# DUTchMate_rev_a.net
KiCad netlist of a schematic drawn in EAGLE
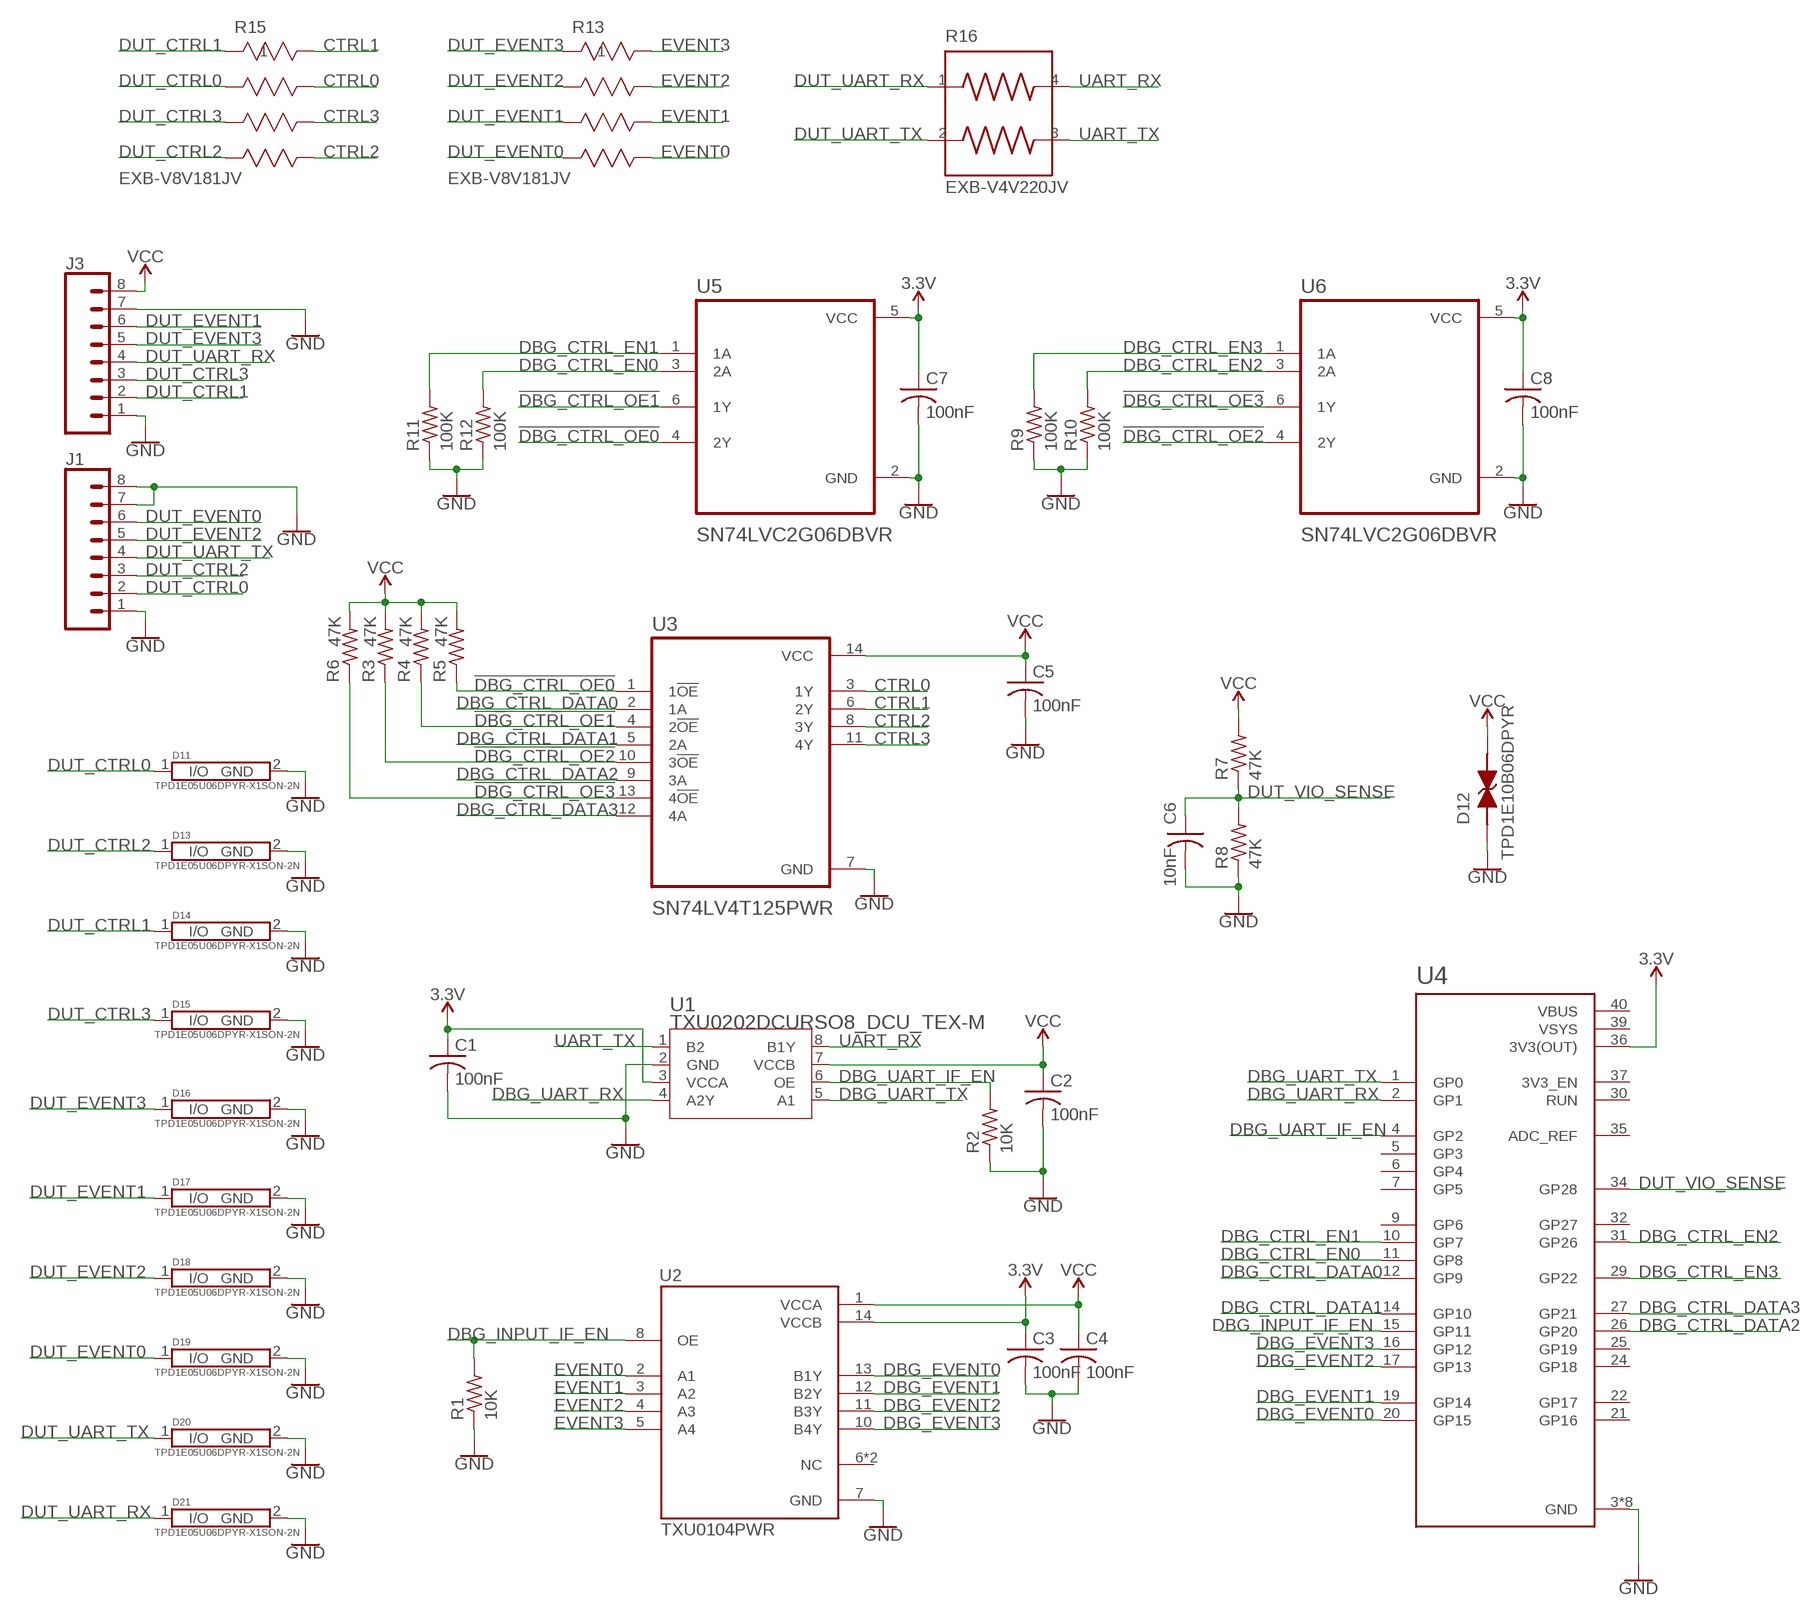
[diagram p0: schematic, sheet 1]

(export (version "E")
  (design (tool "Eeschema 10.0.6"))
  (components
    (comp (ref "C1")
      (value "100nF")
      (footprint "eagle-import:C0805K")
      (libsource (lib "eagle-import") (part "C-USC0805K"))
    )
    (comp (ref "C2")
      (value "100nF")
      (footprint "eagle-import:C0805K")
      (libsource (lib "eagle-import") (part "C-USC0805K"))
    )
    (comp (ref "C3")
      (value "100nF")
      (footprint "eagle-import:C0805K")
      (libsource (lib "eagle-import") (part "C-USC0805K"))
    )
    (comp (ref "C4")
      (value "100nF")
      (footprint "eagle-import:C0805K")
      (libsource (lib "eagle-import") (part "C-USC0805K"))
    )
    (comp (ref "C5")
      (value "100nF")
      (footprint "eagle-import:C0805K")
      (libsource (lib "eagle-import") (part "C-USC0805K"))
    )
    (comp (ref "C6")
      (value "10nF")
      (footprint "eagle-import:C0805K")
      (libsource (lib "eagle-import") (part "C-USC0805K"))
    )
    (comp (ref "C7")
      (value "100nF")
      (footprint "eagle-import:C0805K")
      (libsource (lib "eagle-import") (part "C-USC0805K"))
    )
    (comp (ref "C8")
      (value "100nF")
      (footprint "eagle-import:C0805K")
      (libsource (lib "eagle-import") (part "C-USC0805K"))
    )
    (comp (ref "D11")
      (value "TPD1E05U06DPYR-X1SON-2N")
      (footprint "eagle-import:X1SON-2N")
      (libsource (lib "eagle-import") (part "TPD1E05U06DPYR-X1SON-2N"))
    )
    (comp (ref "D12")
      (value "TPD1E10B06DPYR")
      (footprint "eagle-import:DIO_TPD1E10B06DPYR")
      (fields (field (name "MF") "Texas Instruments"))
      (libsource (lib "eagle-import") (part "TPD1E10B06DPYR"))
    )
    (comp (ref "D13")
      (value "TPD1E05U06DPYR-X1SON-2N")
      (footprint "eagle-import:X1SON-2N")
      (libsource (lib "eagle-import") (part "TPD1E05U06DPYR-X1SON-2N"))
    )
    (comp (ref "D14")
      (value "TPD1E05U06DPYR-X1SON-2N")
      (footprint "eagle-import:X1SON-2N")
      (libsource (lib "eagle-import") (part "TPD1E05U06DPYR-X1SON-2N"))
    )
    (comp (ref "D15")
      (value "TPD1E05U06DPYR-X1SON-2N")
      (footprint "eagle-import:X1SON-2N")
      (libsource (lib "eagle-import") (part "TPD1E05U06DPYR-X1SON-2N"))
    )
    (comp (ref "D16")
      (value "TPD1E05U06DPYR-X1SON-2N")
      (footprint "eagle-import:X1SON-2N")
      (libsource (lib "eagle-import") (part "TPD1E05U06DPYR-X1SON-2N"))
    )
    (comp (ref "D17")
      (value "TPD1E05U06DPYR-X1SON-2N")
      (footprint "eagle-import:X1SON-2N")
      (libsource (lib "eagle-import") (part "TPD1E05U06DPYR-X1SON-2N"))
    )
    (comp (ref "D18")
      (value "TPD1E05U06DPYR-X1SON-2N")
      (footprint "eagle-import:X1SON-2N")
      (libsource (lib "eagle-import") (part "TPD1E05U06DPYR-X1SON-2N"))
    )
    (comp (ref "D19")
      (value "TPD1E05U06DPYR-X1SON-2N")
      (footprint "eagle-import:X1SON-2N")
      (libsource (lib "eagle-import") (part "TPD1E05U06DPYR-X1SON-2N"))
    )
    (comp (ref "D20")
      (value "TPD1E05U06DPYR-X1SON-2N")
      (footprint "eagle-import:X1SON-2N")
      (libsource (lib "eagle-import") (part "TPD1E05U06DPYR-X1SON-2N"))
    )
    (comp (ref "D21")
      (value "TPD1E05U06DPYR-X1SON-2N")
      (footprint "eagle-import:X1SON-2N")
      (libsource (lib "eagle-import") (part "TPD1E05U06DPYR-X1SON-2N"))
    )
    (comp (ref "J1")
      (value "CONN_08NO_SILK_FEMALE_PTH")
      (footprint "eagle-import:1X08_NO_SILK")
      (libsource (lib "eagle-import") (part "CONN_08NO_SILK_FEMALE_PTH"))
    )
    (comp (ref "J3")
      (value "CONN_08NO_SILK_FEMALE_PTH")
      (footprint "eagle-import:1X08_NO_SILK")
      (libsource (lib "eagle-import") (part "CONN_08NO_SILK_FEMALE_PTH"))
    )
    (comp (ref "R1")
      (value "10K")
      (footprint "eagle-import:R0603")
      (libsource (lib "eagle-import") (part "R-US_R0603"))
    )
    (comp (ref "R2")
      (value "10K")
      (footprint "eagle-import:R0603")
      (libsource (lib "eagle-import") (part "R-US_R0603"))
    )
    (comp (ref "R3")
      (value "47K")
      (footprint "eagle-import:R0603")
      (libsource (lib "eagle-import") (part "R-US_R0603"))
    )
    (comp (ref "R4")
      (value "47K")
      (footprint "eagle-import:R0603")
      (libsource (lib "eagle-import") (part "R-US_R0603"))
    )
    (comp (ref "R5")
      (value "47K")
      (footprint "eagle-import:R0603")
      (libsource (lib "eagle-import") (part "R-US_R0603"))
    )
    (comp (ref "R6")
      (value "47K")
      (footprint "eagle-import:R0603")
      (libsource (lib "eagle-import") (part "R-US_R0603"))
    )
    (comp (ref "R7")
      (value "47K")
      (footprint "eagle-import:R0603")
      (libsource (lib "eagle-import") (part "R-US_R0603"))
    )
    (comp (ref "R8")
      (value "47K")
      (footprint "eagle-import:R0603")
      (libsource (lib "eagle-import") (part "R-US_R0603"))
    )
    (comp (ref "R9")
      (value "100K")
      (footprint "eagle-import:R0603")
      (libsource (lib "eagle-import") (part "R-US_R0603"))
    )
    (comp (ref "R10")
      (value "100K")
      (footprint "eagle-import:R0603")
      (libsource (lib "eagle-import") (part "R-US_R0603"))
    )
    (comp (ref "R11")
      (value "100K")
      (footprint "eagle-import:R0603")
      (libsource (lib "eagle-import") (part "R-US_R0603"))
    )
    (comp (ref "R12")
      (value "100K")
      (footprint "eagle-import:R0603")
      (libsource (lib "eagle-import") (part "R-US_R0603"))
    )
    (comp (ref "R13")
      (value "EXB-V8V181JV")
      (footprint "eagle-import:EXBV8V_PAN-M")
      (fields
        (field (name "MANUFACTURER_PART_NUMBER") "EXB-V8V102JV")
        (field (name "COPYRIGHT") "Copyright (C) 2026 Ultra Librarian. All rights reserved.")
      )
      (libsource (lib "eagle-import") (part "EXB-V8V102JVEXBV8V_PAN-M"))
    )
    (comp (ref "R15")
      (value "EXB-V8V181JV")
      (footprint "eagle-import:EXBV8V_PAN-M")
      (fields
        (field (name "MANUFACTURER_PART_NUMBER") "EXB-V8V102JV")
        (field (name "COPYRIGHT") "Copyright (C) 2026 Ultra Librarian. All rights reserved.")
      )
      (libsource (lib "eagle-import") (part "EXB-V8V102JVEXBV8V_PAN-M"))
    )
    (comp (ref "R16")
      (value "EXB-V4V220JV")
      (footprint "eagle-import:RESCAV80P160X160X70-4N")
      (fields
        (field (name "DIGIKEY_PART_NUMBER") "Y2472CT-ND")
        (field (name "MF") "Panasonic")
        (field (name "MP") "EXBV4V472JV")
      )
      (libsource (lib "eagle-import") (part "EXB-V4V472JV"))
    )
    (comp (ref "U1")
      (value "TXU0202DCURSO8_DCU_TEX-M")
      (footprint "eagle-import:SO8_DCU_TEX-M")
      (fields
        (field (name "MANUFACTURER_PART_NUMBER") "TXU0202DCUR")
        (field (name "COPYRIGHT") "Copyright (C) 2026 Ultra Librarian. All rights reserved.")
      )
      (libsource (lib "eagle-import") (part "TXU0202DCURSO8_DCU_TEX-M"))
    )
    (comp (ref "U2")
      (value "TXU0104PWR")
      (footprint "eagle-import:SOP65P640X120-14N")
      (fields (field (name "MF") "Texas Instruments"))
      (libsource (lib "eagle-import") (part "TXU0104PWR"))
    )
    (comp (ref "U3")
      (value "SN74LV4T125PWR")
      (footprint "eagle-import:SOP65P640X120-14N")
      (fields (field (name "MF") "Texas Instruments"))
      (libsource (lib "eagle-import") (part "SN74LV4T125PWR"))
    )
    (comp (ref "U4")
      (value "RASPBERRY_PICO-NO_DEBUGPICO-PKG-TH-NO_DEBUG")
      (footprint "eagle-import:PICO-PKG-TH")
      (libsource (lib "eagle-import") (part "RASPBERRY_PICO-NO_DEBUGPICO-PKG-TH-NO_DEBUG"))
    )
    (comp (ref "U5")
      (value "SN74LVC2G06DBVR")
      (footprint "eagle-import:SOT95P280X145-6N")
      (fields (field (name "MF") "Texas Instruments"))
      (libsource (lib "eagle-import") (part "SN74LVC2G06DBVR"))
    )
    (comp (ref "U6")
      (value "SN74LVC2G06DBVR")
      (footprint "eagle-import:SOT95P280X145-6N")
      (fields (field (name "MF") "Texas Instruments"))
      (libsource (lib "eagle-import") (part "SN74LVC2G06DBVR"))
    )
  )
  (nets
    (net (code "1") (name "/CTRL0") (class "Default")
      (node (ref "R15") (pin "7") (pinfunction "7_7") (pintype "passive"))
      (node (ref "U3") (pin "3") (pinfunction "1Y_3") (pintype "output"))
    )
    (net (code "2") (name "/CTRL1") (class "Default")
      (node (ref "R15") (pin "8") (pinfunction "8_8") (pintype "passive"))
      (node (ref "U3") (pin "6") (pinfunction "2Y_6") (pintype "output"))
    )
    (net (code "3") (name "/CTRL2") (class "Default")
      (node (ref "R15") (pin "5") (pinfunction "5_5") (pintype "passive"))
      (node (ref "U3") (pin "8") (pinfunction "3Y_8") (pintype "output"))
    )
    (net (code "4") (name "/CTRL3") (class "Default")
      (node (ref "R15") (pin "6") (pinfunction "6_6") (pintype "passive"))
      (node (ref "U3") (pin "11") (pinfunction "4Y_11") (pintype "output"))
    )
    (net (code "5") (name "/DBG_CTRL_DATA0") (class "Default")
      (node (ref "U3") (pin "2") (pinfunction "1A_2") (pintype "input"))
      (node (ref "U4") (pin "12") (pinfunction "GP9_12") (pintype "bidirectional"))
    )
    (net (code "6") (name "/DBG_CTRL_DATA1") (class "Default")
      (node (ref "U3") (pin "5") (pinfunction "2A_5") (pintype "input"))
      (node (ref "U4") (pin "14") (pinfunction "GP10_14") (pintype "bidirectional"))
    )
    (net (code "7") (name "/DBG_CTRL_DATA2") (class "Default")
      (node (ref "U3") (pin "9") (pinfunction "3A_9") (pintype "input"))
      (node (ref "U4") (pin "26") (pinfunction "GP20_26") (pintype "bidirectional"))
    )
    (net (code "8") (name "/DBG_CTRL_DATA3") (class "Default")
      (node (ref "U3") (pin "12") (pinfunction "4A_12") (pintype "input"))
      (node (ref "U4") (pin "27") (pinfunction "GP21_27") (pintype "bidirectional"))
    )
    (net (code "9") (name "/DBG_CTRL_EN0") (class "Default")
      (node (ref "R12") (pin "2") (pinfunction "2_2") (pintype "passive"))
      (node (ref "U4") (pin "11") (pinfunction "GP8_11") (pintype "bidirectional"))
      (node (ref "U5") (pin "3") (pinfunction "2A_3") (pintype "input"))
    )
    (net (code "10") (name "/DBG_CTRL_EN1") (class "Default")
      (node (ref "R11") (pin "2") (pinfunction "2_2") (pintype "passive"))
      (node (ref "U4") (pin "10") (pinfunction "GP7_10") (pintype "bidirectional"))
      (node (ref "U5") (pin "1") (pinfunction "1A_1") (pintype "input"))
    )
    (net (code "11") (name "/DBG_CTRL_EN2") (class "Default")
      (node (ref "R10") (pin "2") (pinfunction "2_2") (pintype "passive"))
      (node (ref "U4") (pin "31") (pinfunction "GP26_31") (pintype "bidirectional"))
      (node (ref "U6") (pin "3") (pinfunction "2A_3") (pintype "input"))
    )
    (net (code "12") (name "/DBG_CTRL_EN3") (class "Default")
      (node (ref "R9") (pin "2") (pinfunction "2_2") (pintype "passive"))
      (node (ref "U4") (pin "29") (pinfunction "GP22_29") (pintype "bidirectional"))
      (node (ref "U6") (pin "1") (pinfunction "1A_1") (pintype "input"))
    )
    (net (code "13") (name "/DBG_EVENT0") (class "Default")
      (node (ref "U2") (pin "13") (pinfunction "B1Y_13") (pintype "output"))
      (node (ref "U4") (pin "20") (pinfunction "GP15_20") (pintype "bidirectional"))
    )
    (net (code "14") (name "/DBG_EVENT1") (class "Default")
      (node (ref "U2") (pin "12") (pinfunction "B2Y_12") (pintype "output"))
      (node (ref "U4") (pin "19") (pinfunction "GP14_19") (pintype "bidirectional"))
    )
    (net (code "15") (name "/DBG_EVENT2") (class "Default")
      (node (ref "U2") (pin "11") (pinfunction "B3Y_11") (pintype "output"))
      (node (ref "U4") (pin "17") (pinfunction "GP13_17") (pintype "bidirectional"))
    )
    (net (code "16") (name "/DBG_EVENT3") (class "Default")
      (node (ref "U2") (pin "10") (pinfunction "B4Y_10") (pintype "output"))
      (node (ref "U4") (pin "16") (pinfunction "GP12_16") (pintype "bidirectional"))
    )
    (net (code "17") (name "/DBG_INPUT_IF_EN") (class "Default")
      (node (ref "R1") (pin "2") (pinfunction "2_2") (pintype "passive"))
      (node (ref "U2") (pin "8") (pinfunction "OE_8") (pintype "input"))
      (node (ref "U4") (pin "15") (pinfunction "GP11_15") (pintype "bidirectional"))
    )
    (net (code "18") (name "/DBG_UART_IF_EN") (class "Default")
      (node (ref "R2") (pin "2") (pinfunction "2_2") (pintype "passive"))
      (node (ref "U1") (pin "6") (pinfunction "OE_6") (pintype "input"))
      (node (ref "U4") (pin "4") (pinfunction "GP2_4") (pintype "bidirectional"))
    )
    (net (code "19") (name "/DBG_UART_RX") (class "Default")
      (node (ref "U1") (pin "4") (pinfunction "A2Y_4") (pintype "output"))
      (node (ref "U4") (pin "2") (pinfunction "GP1_2") (pintype "bidirectional"))
    )
    (net (code "20") (name "/DBG_UART_TX") (class "Default")
      (node (ref "U1") (pin "5") (pinfunction "A1_5") (pintype "input"))
      (node (ref "U4") (pin "1") (pinfunction "GP0_1") (pintype "bidirectional"))
    )
    (net (code "21") (name "/DUT_CTRL0") (class "Default")
      (node (ref "D11") (pin "1") (pinfunction "I/O_1") (pintype "bidirectional"))
      (node (ref "J1") (pin "2") (pinfunction "2_2") (pintype "passive"))
      (node (ref "R15") (pin "2") (pinfunction "2_2") (pintype "passive"))
    )
    (net (code "22") (name "/DUT_CTRL1") (class "Default")
      (node (ref "D14") (pin "1") (pinfunction "I/O_1") (pintype "bidirectional"))
      (node (ref "J3") (pin "2") (pinfunction "2_2") (pintype "passive"))
      (node (ref "R15") (pin "1") (pinfunction "1_1") (pintype "passive"))
    )
    (net (code "23") (name "/DUT_CTRL2") (class "Default")
      (node (ref "D13") (pin "1") (pinfunction "I/O_1") (pintype "bidirectional"))
      (node (ref "J1") (pin "3") (pinfunction "3_3") (pintype "passive"))
      (node (ref "R15") (pin "4") (pinfunction "4_4") (pintype "passive"))
    )
    (net (code "24") (name "/DUT_CTRL3") (class "Default")
      (node (ref "D15") (pin "1") (pinfunction "I/O_1") (pintype "bidirectional"))
      (node (ref "J3") (pin "3") (pinfunction "3_3") (pintype "passive"))
      (node (ref "R15") (pin "3") (pinfunction "3_3") (pintype "passive"))
    )
    (net (code "25") (name "/DUT_EVENT0") (class "Default")
      (node (ref "D19") (pin "1") (pinfunction "I/O_1") (pintype "bidirectional"))
      (node (ref "J1") (pin "6") (pinfunction "6_6") (pintype "passive"))
      (node (ref "R13") (pin "4") (pinfunction "4_4") (pintype "passive"))
    )
    (net (code "26") (name "/DUT_EVENT1") (class "Default")
      (node (ref "D17") (pin "1") (pinfunction "I/O_1") (pintype "bidirectional"))
      (node (ref "J3") (pin "6") (pinfunction "6_6") (pintype "passive"))
      (node (ref "R13") (pin "3") (pinfunction "3_3") (pintype "passive"))
    )
    (net (code "27") (name "/DUT_EVENT2") (class "Default")
      (node (ref "D18") (pin "1") (pinfunction "I/O_1") (pintype "bidirectional"))
      (node (ref "J1") (pin "5") (pinfunction "5_5") (pintype "passive"))
      (node (ref "R13") (pin "2") (pinfunction "2_2") (pintype "passive"))
    )
    (net (code "28") (name "/DUT_EVENT3") (class "Default")
      (node (ref "D16") (pin "1") (pinfunction "I/O_1") (pintype "bidirectional"))
      (node (ref "J3") (pin "5") (pinfunction "5_5") (pintype "passive"))
      (node (ref "R13") (pin "1") (pinfunction "1_1") (pintype "passive"))
    )
    (net (code "29") (name "/DUT_UART_RX") (class "Default")
      (node (ref "D21") (pin "1") (pinfunction "I/O_1") (pintype "bidirectional"))
      (node (ref "J3") (pin "4") (pinfunction "4_4") (pintype "passive"))
      (node (ref "R16") (pin "1") (pinfunction "1_1") (pintype "passive"))
    )
    (net (code "30") (name "/DUT_UART_TX") (class "Default")
      (node (ref "D20") (pin "1") (pinfunction "I/O_1") (pintype "bidirectional"))
      (node (ref "J1") (pin "4") (pinfunction "4_4") (pintype "passive"))
      (node (ref "R16") (pin "2") (pinfunction "2_2") (pintype "passive"))
    )
    (net (code "31") (name "/DUT_VIO_SENSE") (class "Default")
      (node (ref "C6") (pin "1") (pinfunction "1_1") (pintype "passive"))
      (node (ref "R7") (pin "1") (pinfunction "1_1") (pintype "passive"))
      (node (ref "R8") (pin "2") (pinfunction "2_2") (pintype "passive"))
      (node (ref "U4") (pin "34") (pinfunction "GP28_34") (pintype "bidirectional"))
    )
    (net (code "32") (name "/EVENT0") (class "Default")
      (node (ref "R13") (pin "5") (pinfunction "5_5") (pintype "passive"))
      (node (ref "U2") (pin "2") (pinfunction "A1_2") (pintype "input"))
    )
    (net (code "33") (name "/EVENT1") (class "Default")
      (node (ref "R13") (pin "6") (pinfunction "6_6") (pintype "passive"))
      (node (ref "U2") (pin "3") (pinfunction "A2_3") (pintype "input"))
    )
    (net (code "34") (name "/EVENT2") (class "Default")
      (node (ref "R13") (pin "7") (pinfunction "7_7") (pintype "passive"))
      (node (ref "U2") (pin "4") (pinfunction "A3_4") (pintype "input"))
    )
    (net (code "35") (name "/EVENT3") (class "Default")
      (node (ref "R13") (pin "8") (pinfunction "8_8") (pintype "passive"))
      (node (ref "U2") (pin "5") (pinfunction "A4_5") (pintype "input"))
    )
    (net (code "36") (name "/UART_RX") (class "Default")
      (node (ref "R16") (pin "4") (pinfunction "4_4") (pintype "passive"))
      (node (ref "U1") (pin "8") (pinfunction "B1Y_8") (pintype "output"))
    )
    (net (code "37") (name "/UART_TX") (class "Default")
      (node (ref "R16") (pin "3") (pinfunction "3_3") (pintype "passive"))
      (node (ref "U1") (pin "1") (pinfunction "B2_1") (pintype "input"))
    )
    (net (code "38") (name "/VBUS") (class "Default")
      (node (ref "U4") (pin "40") (pinfunction "VBUS_40") (pintype "power_in"))
    )
    (net (code "39") (name "/VSYS") (class "Default")
      (node (ref "U4") (pin "39") (pinfunction "VSYS_39") (pintype "power_in"))
    )
    (net (code "40") (name "/~{DBG_CTRL_OE0}") (class "Default")
      (node (ref "R5") (pin "1") (pinfunction "1_1") (pintype "passive"))
      (node (ref "U3") (pin "1") (pinfunction "1~{OE}_1") (pintype "input"))
      (node (ref "U5") (pin "4") (pinfunction "2Y_4") (pintype "bidirectional"))
    )
    (net (code "41") (name "/~{DBG_CTRL_OE1}") (class "Default")
      (node (ref "R4") (pin "1") (pinfunction "1_1") (pintype "passive"))
      (node (ref "U3") (pin "4") (pinfunction "2~{OE}_4") (pintype "input"))
      (node (ref "U5") (pin "6") (pinfunction "1Y_6") (pintype "bidirectional"))
    )
    (net (code "42") (name "/~{DBG_CTRL_OE2}") (class "Default")
      (node (ref "R3") (pin "1") (pinfunction "1_1") (pintype "passive"))
      (node (ref "U3") (pin "10") (pinfunction "3~{OE}_10") (pintype "input"))
      (node (ref "U6") (pin "4") (pinfunction "2Y_4") (pintype "bidirectional"))
    )
    (net (code "43") (name "/~{DBG_CTRL_OE3}") (class "Default")
      (node (ref "R6") (pin "1") (pinfunction "1_1") (pintype "passive"))
      (node (ref "U3") (pin "13") (pinfunction "4~{OE}_13") (pintype "input"))
      (node (ref "U6") (pin "6") (pinfunction "1Y_6") (pintype "bidirectional"))
    )
    (net (code "44") (name "3.3V") (class "Default")
      (node (ref "C1") (pin "1") (pinfunction "1_1") (pintype "passive"))
      (node (ref "C3") (pin "1") (pinfunction "1_1") (pintype "passive"))
      (node (ref "C7") (pin "1") (pinfunction "1_1") (pintype "passive"))
      (node (ref "C8") (pin "1") (pinfunction "1_1") (pintype "passive"))
      (node (ref "U1") (pin "3") (pinfunction "VCCA_3") (pintype "power_in"))
      (node (ref "U2") (pin "14") (pinfunction "VCCB_14") (pintype "power_in"))
      (node (ref "U4") (pin "36") (pinfunction "3V3(OUT)_36") (pintype "power_in"))
      (node (ref "U5") (pin "5") (pinfunction "VCC_5") (pintype "power_in"))
      (node (ref "U6") (pin "5") (pinfunction "VCC_5") (pintype "power_in"))
    )
    (net (code "45") (name "GND") (class "Default")
      (node (ref "C1") (pin "2") (pinfunction "2_2") (pintype "passive"))
      (node (ref "C2") (pin "2") (pinfunction "2_2") (pintype "passive"))
      (node (ref "C3") (pin "2") (pinfunction "2_2") (pintype "passive"))
      (node (ref "C4") (pin "2") (pinfunction "2_2") (pintype "passive"))
      (node (ref "C5") (pin "2") (pinfunction "2_2") (pintype "passive"))
      (node (ref "C6") (pin "2") (pinfunction "2_2") (pintype "passive"))
      (node (ref "C7") (pin "2") (pinfunction "2_2") (pintype "passive"))
      (node (ref "C8") (pin "2") (pinfunction "2_2") (pintype "passive"))
      (node (ref "D11") (pin "2") (pinfunction "GND_2") (pintype "power_in"))
      (node (ref "D12") (pin "1") (pinfunction "1_1") (pintype "passive"))
      (node (ref "D13") (pin "2") (pinfunction "GND_2") (pintype "power_in"))
      (node (ref "D14") (pin "2") (pinfunction "GND_2") (pintype "power_in"))
      (node (ref "D15") (pin "2") (pinfunction "GND_2") (pintype "power_in"))
      (node (ref "D16") (pin "2") (pinfunction "GND_2") (pintype "power_in"))
      (node (ref "D17") (pin "2") (pinfunction "GND_2") (pintype "power_in"))
      (node (ref "D18") (pin "2") (pinfunction "GND_2") (pintype "power_in"))
      (node (ref "D19") (pin "2") (pinfunction "GND_2") (pintype "power_in"))
      (node (ref "D20") (pin "2") (pinfunction "GND_2") (pintype "power_in"))
      (node (ref "D21") (pin "2") (pinfunction "GND_2") (pintype "power_in"))
      (node (ref "J1") (pin "1") (pinfunction "1_1") (pintype "passive"))
      (node (ref "J1") (pin "7") (pinfunction "7_7") (pintype "passive"))
      (node (ref "J1") (pin "8") (pinfunction "8_8") (pintype "passive"))
      (node (ref "J3") (pin "1") (pinfunction "1_1") (pintype "passive"))
      (node (ref "J3") (pin "7") (pinfunction "7_7") (pintype "passive"))
      (node (ref "R1") (pin "1") (pinfunction "1_1") (pintype "passive"))
      (node (ref "R10") (pin "1") (pinfunction "1_1") (pintype "passive"))
      (node (ref "R11") (pin "1") (pinfunction "1_1") (pintype "passive"))
      (node (ref "R12") (pin "1") (pinfunction "1_1") (pintype "passive"))
      (node (ref "R2") (pin "1") (pinfunction "1_1") (pintype "passive"))
      (node (ref "R8") (pin "1") (pinfunction "1_1") (pintype "passive"))
      (node (ref "R9") (pin "1") (pinfunction "1_1") (pintype "passive"))
      (node (ref "U1") (pin "2") (pinfunction "GND_2") (pintype "passive"))
      (node (ref "U2") (pin "7") (pinfunction "GND_7") (pintype "power_in"))
      (node (ref "U3") (pin "7") (pinfunction "GND_7") (pintype "power_in"))
      (node (ref "U4") (pin "13") (pinfunction "GND_13") (pintype "power_in"))
      (node (ref "U4") (pin "18") (pinfunction "GND_18") (pintype "power_in"))
      (node (ref "U4") (pin "23") (pinfunction "GND_23") (pintype "power_in"))
      (node (ref "U4") (pin "28") (pinfunction "GND_28") (pintype "power_in"))
      (node (ref "U4") (pin "3") (pinfunction "GND_3") (pintype "power_in"))
      (node (ref "U4") (pin "33") (pinfunction "GND_33") (pintype "power_in"))
      (node (ref "U4") (pin "38") (pinfunction "GND_38") (pintype "power_in"))
      (node (ref "U4") (pin "8") (pinfunction "GND_8") (pintype "power_in"))
      (node (ref "U5") (pin "2") (pinfunction "GND_2") (pintype "power_in"))
      (node (ref "U6") (pin "2") (pinfunction "GND_2") (pintype "power_in"))
    )
    (net (code "46") (name "VCC") (class "Default")
      (node (ref "C2") (pin "1") (pinfunction "1_1") (pintype "passive"))
      (node (ref "C4") (pin "1") (pinfunction "1_1") (pintype "passive"))
      (node (ref "C5") (pin "1") (pinfunction "1_1") (pintype "passive"))
      (node (ref "D12") (pin "2") (pinfunction "2_2") (pintype "passive"))
      (node (ref "J3") (pin "8") (pinfunction "8_8") (pintype "passive"))
      (node (ref "R3") (pin "2") (pinfunction "2_2") (pintype "passive"))
      (node (ref "R4") (pin "2") (pinfunction "2_2") (pintype "passive"))
      (node (ref "R5") (pin "2") (pinfunction "2_2") (pintype "passive"))
      (node (ref "R6") (pin "2") (pinfunction "2_2") (pintype "passive"))
      (node (ref "R7") (pin "2") (pinfunction "2_2") (pintype "passive"))
      (node (ref "U1") (pin "7") (pinfunction "VCCB_7") (pintype "power_in"))
      (node (ref "U2") (pin "1") (pinfunction "VCCA_1") (pintype "power_in"))
      (node (ref "U3") (pin "14") (pinfunction "VCC_14") (pintype "power_in"))
    )
    (net (code "47") (name "unconnected-(U2-NC-Pad6)") (class "Default")
      (node (ref "U2") (pin "6") (pinfunction "NC_6") (pintype "no_connect"))
    )
    (net (code "48") (name "unconnected-(U2-NC-Pad9)") (class "Default")
      (node (ref "U2") (pin "9") (pinfunction "NC_9") (pintype "no_connect"))
    )
    (net (code "49") (name "unconnected-(U4-3V3_EN-Pad37)") (class "Default")
      (node (ref "U4") (pin "37") (pinfunction "3V3_EN_37") (pintype "input"))
    )
    (net (code "50") (name "unconnected-(U4-ADC_REF-Pad35)") (class "Default")
      (node (ref "U4") (pin "35") (pinfunction "ADC_REF_35") (pintype "input"))
    )
    (net (code "51") (name "unconnected-(U4-GP3-Pad5)") (class "Default")
      (node (ref "U4") (pin "5") (pinfunction "GP3_5") (pintype "bidirectional"))
    )
    (net (code "52") (name "unconnected-(U4-GP4-Pad6)") (class "Default")
      (node (ref "U4") (pin "6") (pinfunction "GP4_6") (pintype "bidirectional"))
    )
    (net (code "53") (name "unconnected-(U4-GP5-Pad7)") (class "Default")
      (node (ref "U4") (pin "7") (pinfunction "GP5_7") (pintype "bidirectional"))
    )
    (net (code "54") (name "unconnected-(U4-GP6-Pad9)") (class "Default")
      (node (ref "U4") (pin "9") (pinfunction "GP6_9") (pintype "bidirectional"))
    )
    (net (code "55") (name "unconnected-(U4-GP16-Pad21)") (class "Default")
      (node (ref "U4") (pin "21") (pinfunction "GP16_21") (pintype "bidirectional"))
    )
    (net (code "56") (name "unconnected-(U4-GP17-Pad22)") (class "Default")
      (node (ref "U4") (pin "22") (pinfunction "GP17_22") (pintype "bidirectional"))
    )
    (net (code "57") (name "unconnected-(U4-GP18-Pad24)") (class "Default")
      (node (ref "U4") (pin "24") (pinfunction "GP18_24") (pintype "bidirectional"))
    )
    (net (code "58") (name "unconnected-(U4-GP19-Pad25)") (class "Default")
      (node (ref "U4") (pin "25") (pinfunction "GP19_25") (pintype "bidirectional"))
    )
    (net (code "59") (name "unconnected-(U4-GP27-Pad32)") (class "Default")
      (node (ref "U4") (pin "32") (pinfunction "GP27_32") (pintype "bidirectional"))
    )
    (net (code "60") (name "unconnected-(U4-RUN-Pad30)") (class "Default")
      (node (ref "U4") (pin "30") (pinfunction "RUN_30") (pintype "input"))
    )
  )
)
